# AST1006.net
KiCad netlist of a schematic drawn in EAGLE
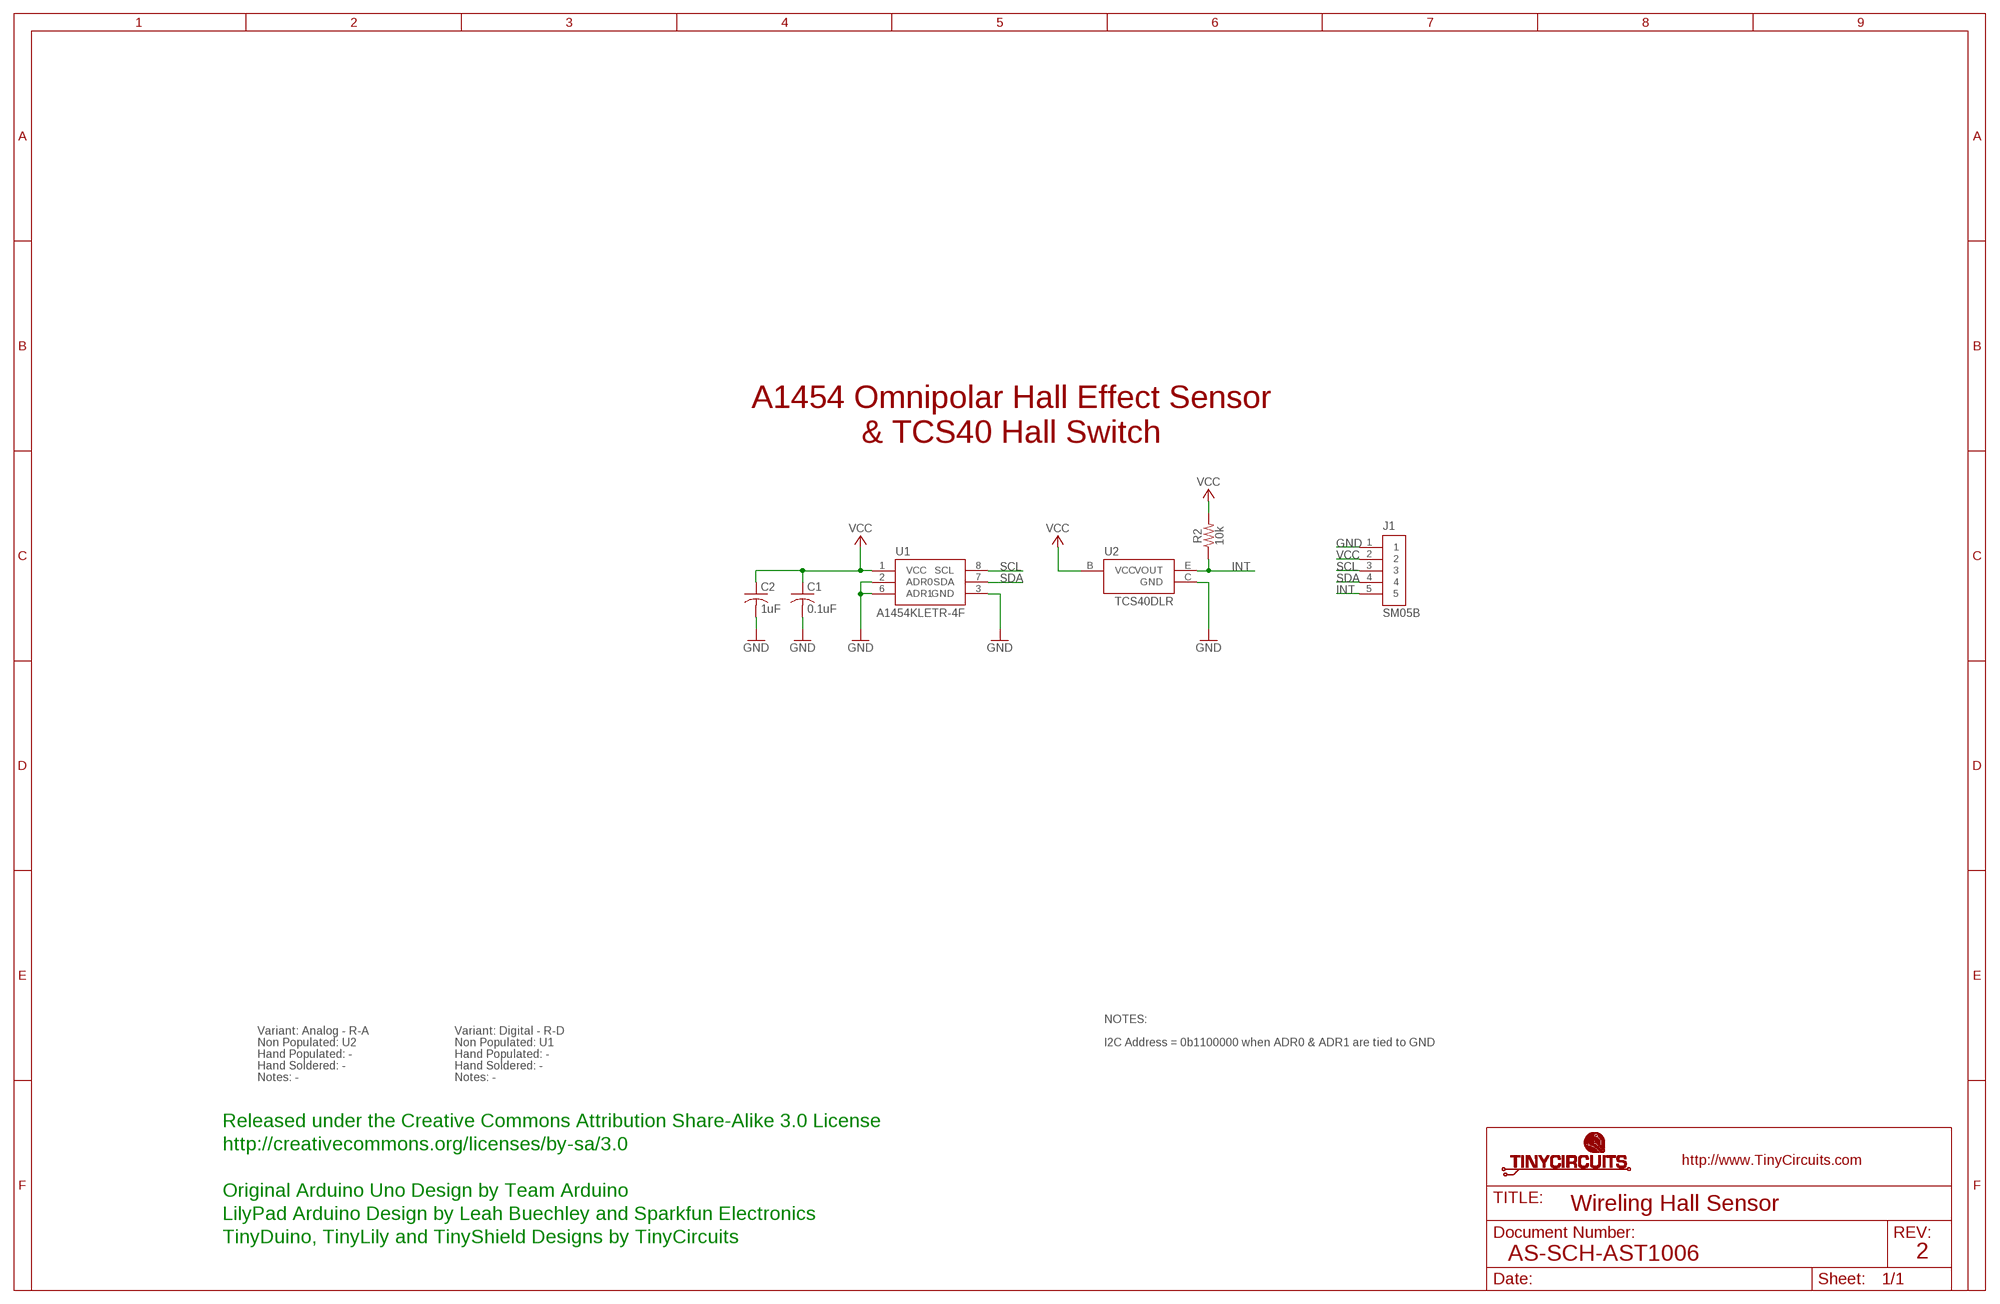
[diagram p0: schematic, sheet 1]

(export (version "E")
  (design (tool "Eeschema 10.0.6"))
  (components
    (comp (ref "C1")
      (value "0.1uF")
      (footprint "eagle-import:C0402")
      (fields (field (name "PARTNO") "AS-ITM-00008"))
      (libsource (lib "eagle-import") (part "AS-ITM-00008"))
    )
    (comp (ref "C2")
      (value "1uF")
      (footprint "eagle-import:C0603")
      (fields (field (name "PARTNO") "AS-ITM-00410") (field (name "PARTNO_1") "AS-ITM-00410"))
      (libsource (lib "eagle-import") (part "AS-ITM-00410"))
    )
    (comp (ref "J1")
      (value "SM05B")
      (footprint "eagle-import:JST_SH_5X1_EDGE")
      (fields (field (name "PARTNO") "AS-ITM-00340"))
      (libsource (lib "eagle-import") (part "AS-ITM-00340EDGE"))
    )
    (comp (ref "R2")
      (value "10k")
      (footprint "eagle-import:0402")
      (fields (field (name "PARTNO") "AS-ITM-00032") (field (name "PARTNO_1") "AS-ITM-00032"))
      (libsource (lib "eagle-import") (part "AS-ITM-00032"))
    )
    (comp (ref "U1")
      (value "A1454KLETR-4F")
      (footprint "eagle-import:TSSOP(8)")
      (fields (field (name "PARTNO") "AS-ITM-00361"))
      (libsource (lib "eagle-import") (part "AS-ITM-00361"))
    )
    (comp (ref "U2")
      (value "TCS40DLR")
      (footprint "eagle-import:SOT23A")
      (fields (field (name "PARTNO") "AS-ITM-00362"))
      (libsource (lib "eagle-import") (part "AS-ITM-00362C"))
    )
  )
  (nets
    (net (code "1") (name "/INT") (class "Default")
      (node (ref "J1") (pin "5") (pinfunction "5_5") (pintype "bidirectional"))
      (node (ref "R2") (pin "1") (pinfunction "1_1") (pintype "passive"))
      (node (ref "U2") (pin "E") (pinfunction "VOUT_E") (pintype "bidirectional"))
    )
    (net (code "2") (name "/SCL") (class "Default")
      (node (ref "J1") (pin "3") (pinfunction "3_3") (pintype "bidirectional"))
      (node (ref "U1") (pin "8") (pinfunction "SCL_8") (pintype "bidirectional"))
    )
    (net (code "3") (name "/SDA") (class "Default")
      (node (ref "J1") (pin "4") (pinfunction "4_4") (pintype "bidirectional"))
      (node (ref "U1") (pin "7") (pinfunction "SDA_7") (pintype "bidirectional"))
    )
    (net (code "4") (name "GND") (class "Default")
      (node (ref "C1") (pin "2") (pinfunction "2_2") (pintype "passive"))
      (node (ref "C2") (pin "2") (pinfunction "2_2") (pintype "passive"))
      (node (ref "J1") (pin "1") (pinfunction "1_1") (pintype "bidirectional"))
      (node (ref "U1") (pin "2") (pinfunction "ADR0_2") (pintype "bidirectional"))
      (node (ref "U1") (pin "3") (pinfunction "GND_3") (pintype "bidirectional"))
      (node (ref "U1") (pin "6") (pinfunction "ADR1_6") (pintype "bidirectional"))
      (node (ref "U2") (pin "C") (pinfunction "GND_C") (pintype "bidirectional"))
    )
    (net (code "5") (name "VCC") (class "Default")
      (node (ref "C1") (pin "1") (pinfunction "1_1") (pintype "passive"))
      (node (ref "C2") (pin "1") (pinfunction "1_1") (pintype "passive"))
      (node (ref "J1") (pin "2") (pinfunction "2_2") (pintype "bidirectional"))
      (node (ref "R2") (pin "2") (pinfunction "2_2") (pintype "passive"))
      (node (ref "U1") (pin "1") (pinfunction "VCC_1") (pintype "bidirectional"))
      (node (ref "U2") (pin "B") (pinfunction "VCC_B") (pintype "bidirectional"))
    )
  )
)
